# CNC.net
KiCad netlist of a schematic drawn in Altium Designer
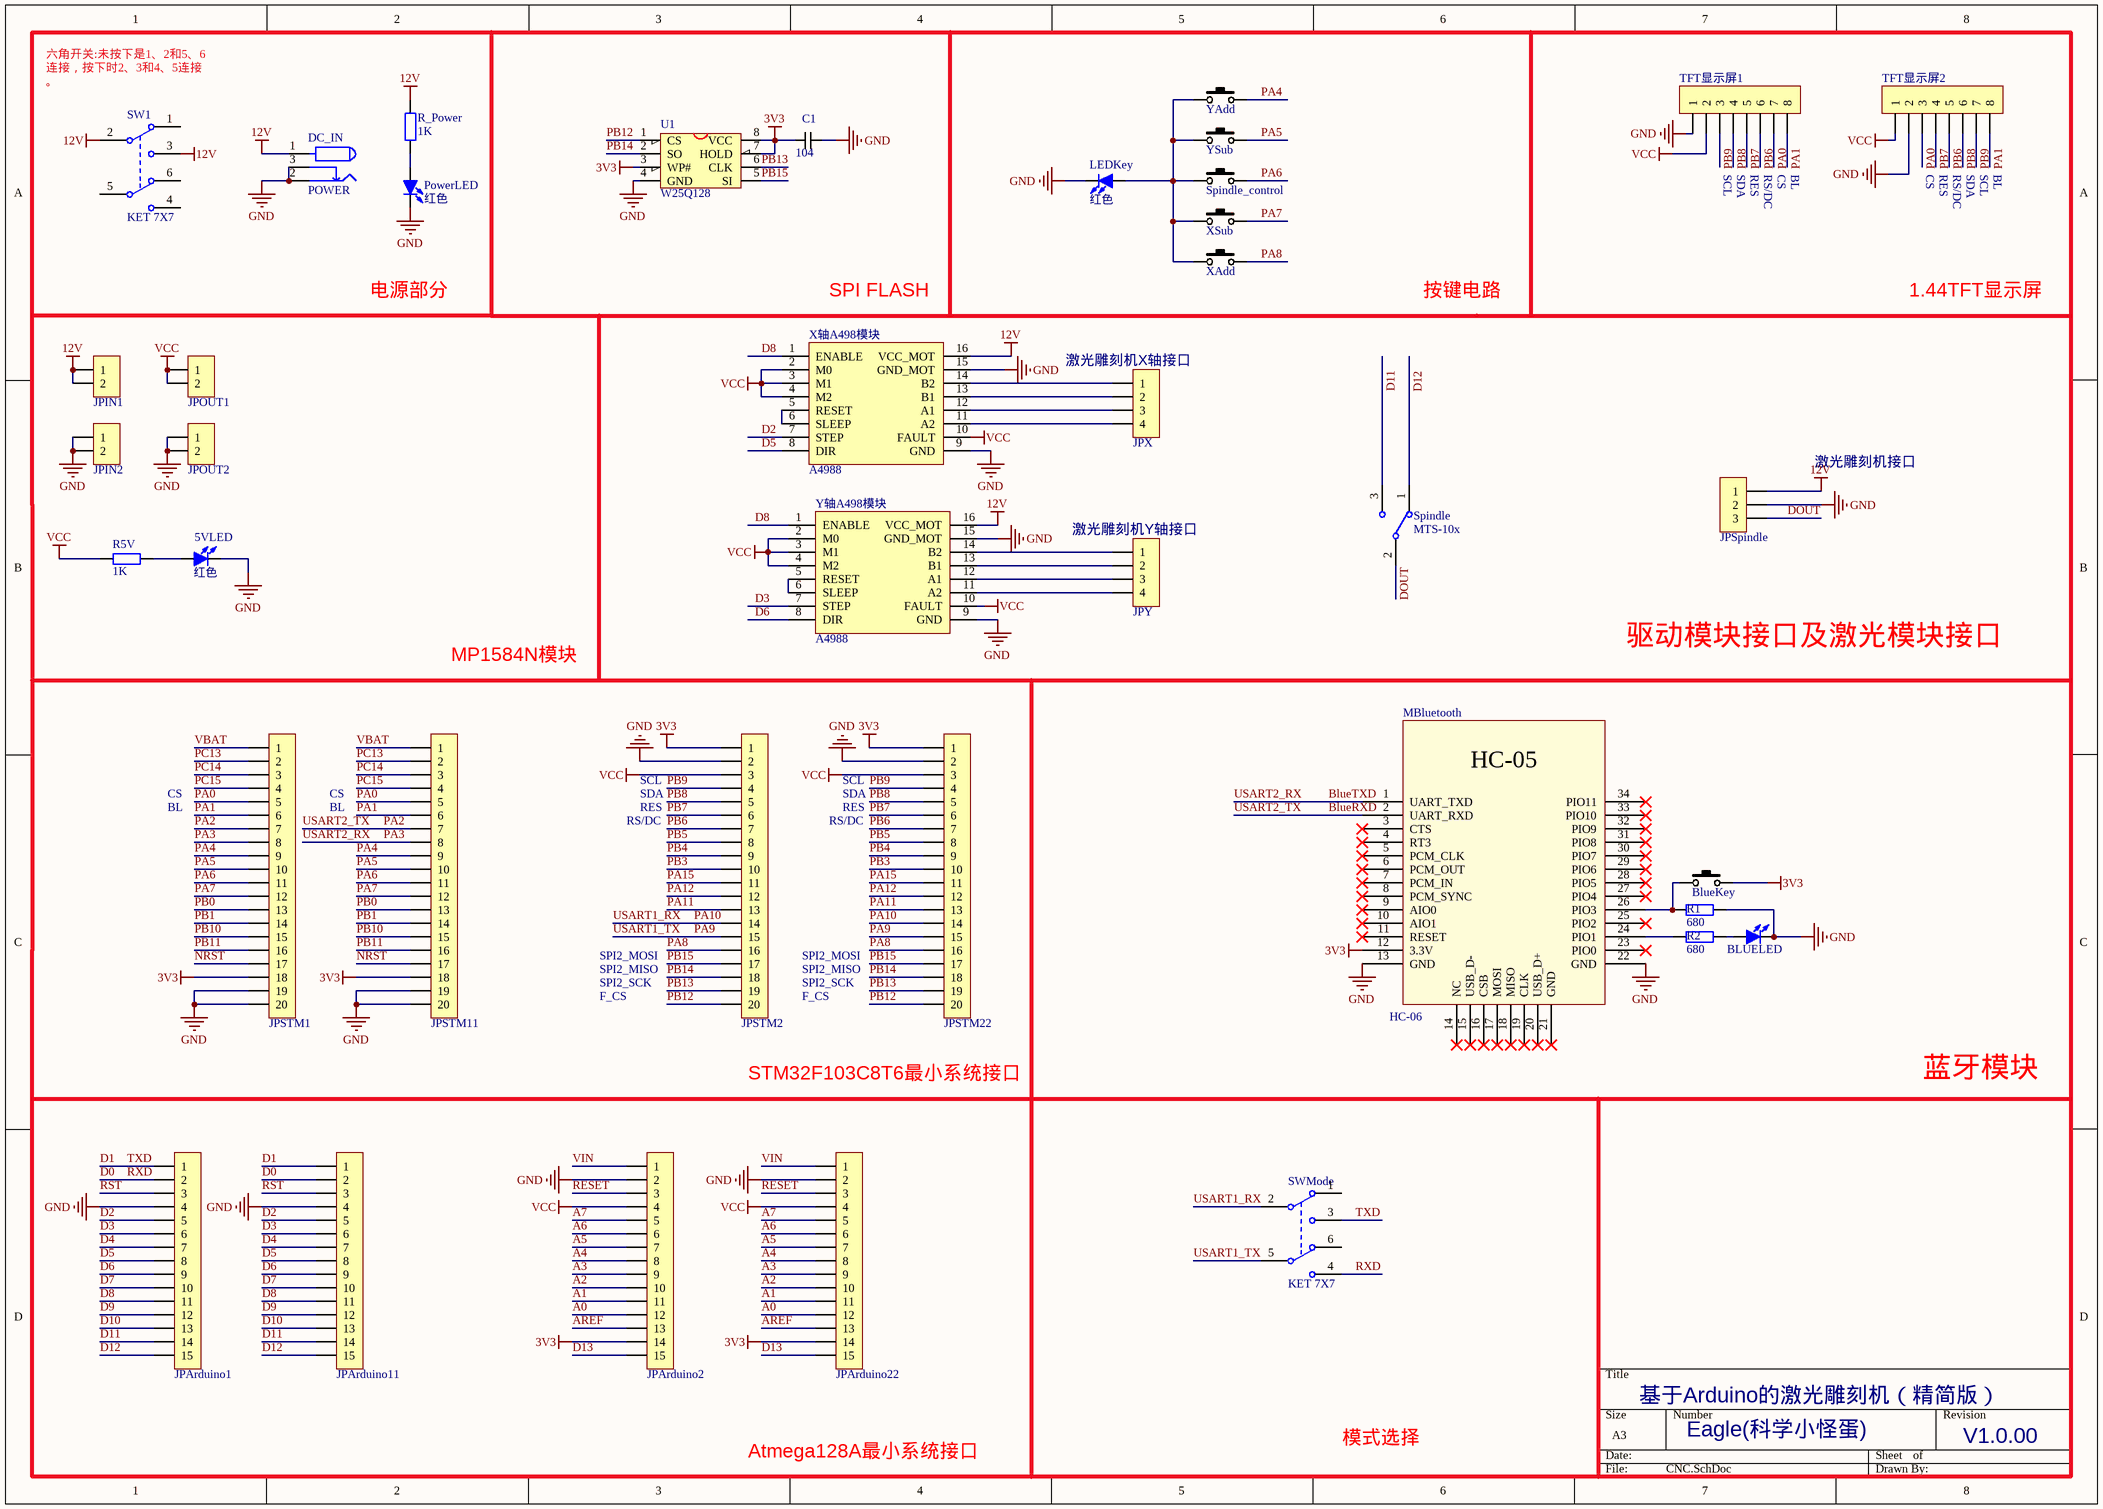
[diagram p0: CNC.SchDoc]

(export (version "E")
  (design (tool "Eeschema 10.0.6"))
  (components
    (comp (ref "5VLED")
      (value "红色")
      (footprint "LED 3MM-B")
      (description "插件LED")
      (fields (field (name "版权归属") "源创客"))
      (libsource (lib "9.1   - LED") (part "LED-3MM"))
    )
    (comp (ref "BlueKey")
      (value "Key")
      (footprint "SW-PB")
      (description "按键")
      (libsource (lib "Component") (part "Key"))
    )
    (comp (ref "BLUELED")
      (value "红色")
      (footprint "LED 0805R")
      (description "贴片LED")
      (fields (field (name "版权归属") "源创客"))
      (libsource (lib "9.1   - LED") (part "LED-SMD"))
    )
    (comp (ref "C1")
      (value "cap")
      (footprint "C0805")
      (description "电容")
      (fields (field (name "ALTIUM_UNNAMED_1") "104"))
      (libsource (lib "Component") (part "Cap"))
    )
    (comp (ref "DC_IN") (value "POWER") (footprint "DC10B") (libsource (lib "WARSHIP") (part "POW")))
    (comp (ref "JPArduino1")
      (value "HDR-1X15")
      (footprint "HDR2.54-LI-15P")
      (description "15P接插件")
      (fields (field (name "版权归属") "源创客"))
      (libsource (lib "4.5   - 接插件-脚距2.54") (part "Header 15"))
    )
    (comp (ref "JPArduino2")
      (value "HDR-1X15")
      (footprint "HDR2.54-LI-15P")
      (description "15P接插件")
      (fields (field (name "版权归属") "源创客"))
      (libsource (lib "4.5   - 接插件-脚距2.54") (part "Header 15"))
    )
    (comp (ref "JPArduino11")
      (value "HDR-1X15")
      (footprint "HDR2.54-LI-15P")
      (description "15P接插件")
      (fields (field (name "版权归属") "源创客"))
      (libsource (lib "4.5   - 接插件-脚距2.54") (part "Header 15"))
    )
    (comp (ref "JPArduino22")
      (value "HDR-1X15")
      (footprint "HDR2.54-LI-15P")
      (description "15P接插件")
      (fields (field (name "版权归属") "源创客"))
      (libsource (lib "4.5   - 接插件-脚距2.54") (part "Header 15"))
    )
    (comp (ref "JPIN1")
      (value "HDR-1X2")
      (footprint "HDR2.54-LI-2P")
      (description "2P接插件")
      (fields (field (name "版权归属") "源创客"))
      (libsource (lib "4.5   - 接插件-脚距2.54") (part "Header 2"))
    )
    (comp (ref "JPIN2")
      (value "HDR-1X2")
      (footprint "HDR2.54-LI-2P")
      (description "2P接插件")
      (fields (field (name "版权归属") "源创客"))
      (libsource (lib "4.5   - 接插件-脚距2.54") (part "Header 2"))
    )
    (comp (ref "JPOUT1")
      (value "HDR-1X2")
      (footprint "HDR2.54-LI-2P")
      (description "2P接插件")
      (fields (field (name "版权归属") "源创客"))
      (libsource (lib "4.5   - 接插件-脚距2.54") (part "Header 2"))
    )
    (comp (ref "JPOUT2")
      (value "HDR-1X2")
      (footprint "HDR2.54-LI-2P")
      (description "2P接插件")
      (fields (field (name "版权归属") "源创客"))
      (libsource (lib "4.5   - 接插件-脚距2.54") (part "Header 2"))
    )
    (comp (ref "JPSpindle")
      (value "HDR-1X3")
      (footprint "XH2.54-WI-3P")
      (description "3P接插件")
      (fields (field (name "版权归属") "源创客"))
      (libsource (lib "4.5   - 接插件-脚距2.54") (part "Header 3"))
    )
    (comp (ref "JPSTM1")
      (value "HDR-1X20")
      (footprint "HDR2.54-LI-20P")
      (description "20P接插件")
      (fields (field (name "版权归属") "源创客"))
      (libsource (lib "4.5   - 接插件-脚距2.54") (part "Header 20"))
    )
    (comp (ref "JPSTM2")
      (value "HDR-1X20")
      (footprint "HDR2.54-LI-20P")
      (description "20P接插件")
      (fields (field (name "版权归属") "源创客"))
      (libsource (lib "4.5   - 接插件-脚距2.54") (part "Header 20"))
    )
    (comp (ref "JPSTM11")
      (value "HDR-1X20")
      (footprint "HDR2.54-LI-20P")
      (description "20P接插件")
      (fields (field (name "版权归属") "源创客"))
      (libsource (lib "4.5   - 接插件-脚距2.54") (part "Header 20"))
    )
    (comp (ref "JPSTM22")
      (value "HDR-1X20")
      (footprint "HDR2.54-LI-20P")
      (description "20P接插件")
      (fields (field (name "版权归属") "源创客"))
      (libsource (lib "4.5   - 接插件-脚距2.54") (part "Header 20"))
    )
    (comp (ref "JPX")
      (value "HDR-1X4")
      (footprint "XH2.54-WI-4P")
      (description "4P接插件")
      (fields (field (name "版权归属") "源创客"))
      (libsource (lib "4.5   - 接插件-脚距2.54") (part "Header 4"))
    )
    (comp (ref "JPY")
      (value "HDR-1X4")
      (footprint "XH2.54-WI-4P")
      (description "4P接插件")
      (fields (field (name "版权归属") "源创客"))
      (libsource (lib "4.5   - 接插件-脚距2.54") (part "Header 4"))
    )
    (comp (ref "LEDKey")
      (value "红色")
      (footprint "LED 5MM-B")
      (description "5mm插件LED")
      (fields (field (name "版权归属") "源创客"))
      (libsource (lib "9.1   - LED") (part "LED-5MM"))
    )
    (comp (ref "MBluetooth")
      (value "HC-06")
      (footprint "HC-05")
      (description "串口蓝牙模块")
      (fields (field (name "版权归属") "源创客"))
      (libsource (lib "13.1 - 模块") (part "HC-05"))
    )
    (comp (ref "PowerLED")
      (value "红色")
      (footprint "LED 3MM-B")
      (description "插件LED")
      (fields (field (name "版权归属") "源创客"))
      (libsource (lib "9.1   - LED") (part "LED-3MM"))
    )
    (comp (ref "R1")
      (value "680")
      (footprint "R 0805_L")
      (description "贴片电阻")
      (fields (field (name "版权归属") "源创客"))
      (libsource (lib "3.1   - 电阻-电容-电感") (part "R"))
    )
    (comp (ref "R2")
      (value "680")
      (footprint "R 0805_L")
      (description "贴片电阻")
      (fields (field (name "版权归属") "源创客"))
      (libsource (lib "3.1   - 电阻-电容-电感") (part "R"))
    )
    (comp (ref "R5V")
      (value "1K")
      (footprint "RS 1/4W")
      (description "直插色环电阻")
      (fields (field (name "版权归属") "源创客"))
      (libsource (lib "3.1   - 电阻-电容-电感") (part "R-CRR"))
    )
    (comp (ref "R_Power")
      (value "1K")
      (footprint "RS 1/4W")
      (description "直插色环电阻")
      (fields (field (name "版权归属") "源创客"))
      (libsource (lib "3.1   - 电阻-电容-电感") (part "R-CRR"))
    )
    (comp (ref "Spindle")
      (value "MTS-10x")
      (footprint "MTS-10x")
      (description "MTS10x系列3脚扭子开关")
      (fields (field (name "版权归属") "源创客"))
      (libsource (lib "5.1   - 按键-开关") (part "MTS-10x"))
    )
    (comp (ref "Spindle_control")
      (value "Key")
      (footprint "SW-PB")
      (description "按键")
      (libsource (lib "Component") (part "Key"))
    )
    (comp (ref "SW1")
      (value "KET 7X7")
      (footprint "KFT DIP-7X7")
      (description "7*7自锁开关")
      (fields (field (name "版权归属") "源创客"))
      (libsource (lib "5.1   - 按键-开关") (part "KET 7X7"))
    )
    (comp (ref "SWMode")
      (value "KET 7X7")
      (footprint "KFT DIP-7X7")
      (description "7*7自锁开关")
      (fields (field (name "版权归属") "源创客"))
      (libsource (lib "5.1   - 按键-开关") (part "KET 7X7"))
    )
    (comp (ref "TFT显示屏1")
      (value "HDR-1X8")
      (footprint "HDR2.54-Y-LI-8P")
      (description "8P接插件")
      (fields (field (name "版权归属") "源创客"))
      (libsource (lib "4.5   - 接插件-脚距2.54") (part "Header 8"))
    )
    (comp (ref "TFT显示屏2")
      (value "HDR-1X8")
      (footprint "HDR2.54-Y-LI-8P")
      (description "8P接插件")
      (fields (field (name "版权归属") "源创客"))
      (libsource (lib "4.5   - 接插件-脚距2.54") (part "Header 8"))
    )
    (comp (ref "U1")
      (value "W25Q128")
      (footprint "SOIC-8")
      (description "W25X16;SST25VF016;MX25L1605")
      (libsource (lib "WARSHIP") (part "W25X16"))
    )
    (comp (ref "XAdd")
      (value "Key")
      (footprint "SW-PB")
      (description "按键")
      (libsource (lib "Component") (part "Key"))
    )
    (comp (ref "XSub")
      (value "Key")
      (footprint "SW-PB")
      (description "按键")
      (libsource (lib "Component") (part "Key"))
    )
    (comp (ref "X轴A498模块")
      (value "A4988")
      (footprint "DRV8825")
      (description "步进电机驱动模块")
      (fields (field (name "版权归属") "源创客"))
      (libsource (lib "13.1 - 模块") (part "DRV8825"))
    )
    (comp (ref "YAdd")
      (value "Key")
      (footprint "SW-PB")
      (description "按键")
      (libsource (lib "Component") (part "Key"))
    )
    (comp (ref "YSub")
      (value "Key")
      (footprint "SW-PB")
      (description "按键")
      (libsource (lib "Component") (part "Key"))
    )
    (comp (ref "Y轴A498模块")
      (value "A4988")
      (footprint "DRV8825")
      (description "步进电机驱动模块")
      (fields (field (name "版权归属") "源创客"))
      (libsource (lib "13.1 - 模块") (part "DRV8825"))
    )
  )
  (nets
    (net (code "1") (name "/A0") (class "Default")
      (node (ref "JPArduino2") (pin "12") (pinfunction "12_12") (pintype "passive"))
      (node (ref "JPArduino22") (pin "12") (pinfunction "12_12") (pintype "passive"))
    )
    (net (code "2") (name "/A1") (class "Default")
      (node (ref "JPArduino2") (pin "11") (pinfunction "11_11") (pintype "passive"))
      (node (ref "JPArduino22") (pin "11") (pinfunction "11_11") (pintype "passive"))
    )
    (net (code "3") (name "/A2") (class "Default")
      (node (ref "JPArduino2") (pin "10") (pinfunction "10_10") (pintype "passive"))
      (node (ref "JPArduino22") (pin "10") (pinfunction "10_10") (pintype "passive"))
    )
    (net (code "4") (name "/A3") (class "Default")
      (node (ref "JPArduino2") (pin "9") (pinfunction "9_9") (pintype "passive"))
      (node (ref "JPArduino22") (pin "9") (pinfunction "9_9") (pintype "passive"))
    )
    (net (code "5") (name "/A4") (class "Default")
      (node (ref "JPArduino2") (pin "8") (pinfunction "8_8") (pintype "passive"))
      (node (ref "JPArduino22") (pin "8") (pinfunction "8_8") (pintype "passive"))
    )
    (net (code "6") (name "/A5") (class "Default")
      (node (ref "JPArduino2") (pin "7") (pinfunction "7_7") (pintype "passive"))
      (node (ref "JPArduino22") (pin "7") (pinfunction "7_7") (pintype "passive"))
    )
    (net (code "7") (name "/A6") (class "Default")
      (node (ref "JPArduino2") (pin "6") (pinfunction "6_6") (pintype "passive"))
      (node (ref "JPArduino22") (pin "6") (pinfunction "6_6") (pintype "passive"))
    )
    (net (code "8") (name "/A7") (class "Default")
      (node (ref "JPArduino2") (pin "5") (pinfunction "5_5") (pintype "passive"))
      (node (ref "JPArduino22") (pin "5") (pinfunction "5_5") (pintype "passive"))
    )
    (net (code "9") (name "/AREF") (class "Default")
      (node (ref "JPArduino2") (pin "13") (pinfunction "13_13") (pintype "passive"))
      (node (ref "JPArduino22") (pin "13") (pinfunction "13_13") (pintype "passive"))
    )
    (net (code "10") (name "/BlueRXD") (class "Default")
      (node (ref "JPSTM1") (pin "7") (pinfunction "7_7") (pintype "passive"))
      (node (ref "JPSTM11") (pin "7") (pinfunction "7_7") (pintype "passive"))
      (node (ref "MBluetooth") (pin "2") (pinfunction "UART_RXD_2") (pintype "passive"))
    )
    (net (code "11") (name "/BlueTXD") (class "Default")
      (node (ref "JPSTM1") (pin "8") (pinfunction "8_8") (pintype "passive"))
      (node (ref "JPSTM11") (pin "8") (pinfunction "8_8") (pintype "passive"))
      (node (ref "MBluetooth") (pin "1") (pinfunction "UART_TXD_1") (pintype "passive"))
    )
    (net (code "12") (name "/D0") (class "Default")
      (node (ref "JPArduino1") (pin "2") (pinfunction "2_2") (pintype "passive"))
      (node (ref "JPArduino11") (pin "2") (pinfunction "2_2") (pintype "passive"))
      (node (ref "SWMode") (pin "4") (pinfunction "NO2_4") (pintype "passive"))
    )
    (net (code "13") (name "/D1") (class "Default")
      (node (ref "JPArduino1") (pin "1") (pinfunction "1_1") (pintype "passive"))
      (node (ref "JPArduino11") (pin "1") (pinfunction "1_1") (pintype "passive"))
      (node (ref "SWMode") (pin "3") (pinfunction "NO1_3") (pintype "passive"))
    )
    (net (code "14") (name "/D2") (class "Default")
      (node (ref "JPArduino1") (pin "5") (pinfunction "5_5") (pintype "passive"))
      (node (ref "JPArduino11") (pin "5") (pinfunction "5_5") (pintype "passive"))
      (node (ref "X轴A498模块") (pin "7") (pinfunction "STEP_7") (pintype "passive"))
    )
    (net (code "15") (name "/D3") (class "Default")
      (node (ref "JPArduino1") (pin "6") (pinfunction "6_6") (pintype "passive"))
      (node (ref "JPArduino11") (pin "6") (pinfunction "6_6") (pintype "passive"))
      (node (ref "Y轴A498模块") (pin "7") (pinfunction "STEP_7") (pintype "passive"))
    )
    (net (code "16") (name "/D4") (class "Default")
      (node (ref "JPArduino1") (pin "7") (pinfunction "7_7") (pintype "passive"))
      (node (ref "JPArduino11") (pin "7") (pinfunction "7_7") (pintype "passive"))
    )
    (net (code "17") (name "/D5") (class "Default")
      (node (ref "JPArduino1") (pin "8") (pinfunction "8_8") (pintype "passive"))
      (node (ref "JPArduino11") (pin "8") (pinfunction "8_8") (pintype "passive"))
      (node (ref "X轴A498模块") (pin "8") (pinfunction "DIR_8") (pintype "passive"))
    )
    (net (code "18") (name "/D6") (class "Default")
      (node (ref "JPArduino1") (pin "9") (pinfunction "9_9") (pintype "passive"))
      (node (ref "JPArduino11") (pin "9") (pinfunction "9_9") (pintype "passive"))
      (node (ref "Y轴A498模块") (pin "8") (pinfunction "DIR_8") (pintype "passive"))
    )
    (net (code "19") (name "/D7") (class "Default")
      (node (ref "JPArduino1") (pin "10") (pinfunction "10_10") (pintype "passive"))
      (node (ref "JPArduino11") (pin "10") (pinfunction "10_10") (pintype "passive"))
    )
    (net (code "20") (name "/D8") (class "Default")
      (node (ref "JPArduino1") (pin "11") (pinfunction "11_11") (pintype "passive"))
      (node (ref "JPArduino11") (pin "11") (pinfunction "11_11") (pintype "passive"))
      (node (ref "X轴A498模块") (pin "1") (pinfunction "ENABLE_1") (pintype "passive"))
      (node (ref "Y轴A498模块") (pin "1") (pinfunction "ENABLE_1") (pintype "passive"))
    )
    (net (code "21") (name "/D9") (class "Default")
      (node (ref "JPArduino1") (pin "12") (pinfunction "12_12") (pintype "passive"))
      (node (ref "JPArduino11") (pin "12") (pinfunction "12_12") (pintype "passive"))
    )
    (net (code "22") (name "/D10") (class "Default")
      (node (ref "JPArduino1") (pin "13") (pinfunction "13_13") (pintype "passive"))
      (node (ref "JPArduino11") (pin "13") (pinfunction "13_13") (pintype "passive"))
    )
    (net (code "23") (name "/D11") (class "Default")
      (node (ref "JPArduino1") (pin "14") (pinfunction "14_14") (pintype "passive"))
      (node (ref "JPArduino11") (pin "14") (pinfunction "14_14") (pintype "passive"))
      (node (ref "Spindle") (pin "3") (pinfunction "3_3") (pintype "passive"))
    )
    (net (code "24") (name "/D12") (class "Default")
      (node (ref "JPArduino1") (pin "15") (pinfunction "15_15") (pintype "passive"))
      (node (ref "JPArduino11") (pin "15") (pinfunction "15_15") (pintype "passive"))
      (node (ref "Spindle") (pin "1") (pinfunction "1_1") (pintype "passive"))
    )
    (net (code "25") (name "/D13") (class "Default")
      (node (ref "JPArduino2") (pin "15") (pinfunction "15_15") (pintype "passive"))
      (node (ref "JPArduino22") (pin "15") (pinfunction "15_15") (pintype "passive"))
    )
    (net (code "26") (name "/DOUT") (class "Default")
      (node (ref "JPSpindle") (pin "3") (pinfunction "3_3") (pintype "passive"))
      (node (ref "Spindle") (pin "2") (pinfunction "2_2") (pintype "passive"))
    )
    (net (code "27") (name "/NRST") (class "Default")
      (node (ref "JPSTM1") (pin "17") (pinfunction "17_17") (pintype "passive"))
      (node (ref "JPSTM11") (pin "17") (pinfunction "17_17") (pintype "passive"))
    )
    (net (code "28") (name "/PA0") (class "Default")
      (node (ref "JPSTM1") (pin "5") (pinfunction "5_5") (pintype "passive"))
      (node (ref "JPSTM11") (pin "5") (pinfunction "5_5") (pintype "passive"))
      (node (ref "TFT显示屏1") (pin "7") (pinfunction "7_7") (pintype "passive"))
      (node (ref "TFT显示屏2") (pin "3") (pinfunction "3_3") (pintype "passive"))
    )
    (net (code "29") (name "/PA1") (class "Default")
      (node (ref "JPSTM1") (pin "6") (pinfunction "6_6") (pintype "passive"))
      (node (ref "JPSTM11") (pin "6") (pinfunction "6_6") (pintype "passive"))
      (node (ref "TFT显示屏1") (pin "8") (pinfunction "8_8") (pintype "passive"))
      (node (ref "TFT显示屏2") (pin "8") (pinfunction "8_8") (pintype "passive"))
    )
    (net (code "30") (name "/PA4") (class "Default")
      (node (ref "JPSTM1") (pin "9") (pinfunction "9_9") (pintype "passive"))
      (node (ref "JPSTM11") (pin "9") (pinfunction "9_9") (pintype "passive"))
      (node (ref "YAdd") (pin "3") (pintype "passive"))
    )
    (net (code "31") (name "/PA5") (class "Default")
      (node (ref "JPSTM1") (pin "10") (pinfunction "10_10") (pintype "passive"))
      (node (ref "JPSTM11") (pin "10") (pinfunction "10_10") (pintype "passive"))
      (node (ref "YSub") (pin "3") (pintype "passive"))
    )
    (net (code "32") (name "/PA6") (class "Default")
      (node (ref "JPSTM1") (pin "11") (pinfunction "11_11") (pintype "passive"))
      (node (ref "JPSTM11") (pin "11") (pinfunction "11_11") (pintype "passive"))
      (node (ref "Spindle_control") (pin "3") (pintype "passive"))
    )
    (net (code "33") (name "/PA7") (class "Default")
      (node (ref "JPSTM1") (pin "12") (pinfunction "12_12") (pintype "passive"))
      (node (ref "JPSTM11") (pin "12") (pinfunction "12_12") (pintype "passive"))
      (node (ref "XSub") (pin "3") (pintype "passive"))
    )
    (net (code "34") (name "/PA8") (class "Default")
      (node (ref "JPSTM2") (pin "16") (pinfunction "16_16") (pintype "passive"))
      (node (ref "JPSTM22") (pin "16") (pinfunction "16_16") (pintype "passive"))
      (node (ref "XAdd") (pin "3") (pintype "passive"))
    )
    (net (code "35") (name "/PA9") (class "Default")
      (node (ref "JPSTM2") (pin "15") (pinfunction "15_15") (pintype "passive"))
      (node (ref "JPSTM22") (pin "15") (pinfunction "15_15") (pintype "passive"))
      (node (ref "SWMode") (pin "5") (pinfunction "COM2_5") (pintype "passive"))
    )
    (net (code "36") (name "/PA10") (class "Default")
      (node (ref "JPSTM2") (pin "14") (pinfunction "14_14") (pintype "passive"))
      (node (ref "JPSTM22") (pin "14") (pinfunction "14_14") (pintype "passive"))
      (node (ref "SWMode") (pin "2") (pinfunction "COM2_2") (pintype "passive"))
    )
    (net (code "37") (name "/PA11") (class "Default")
      (node (ref "JPSTM2") (pin "13") (pinfunction "13_13") (pintype "passive"))
      (node (ref "JPSTM22") (pin "13") (pinfunction "13_13") (pintype "passive"))
    )
    (net (code "38") (name "/PA12") (class "Default")
      (node (ref "JPSTM2") (pin "12") (pinfunction "12_12") (pintype "passive"))
      (node (ref "JPSTM22") (pin "12") (pinfunction "12_12") (pintype "passive"))
    )
    (net (code "39") (name "/PA15") (class "Default")
      (node (ref "JPSTM2") (pin "11") (pinfunction "11_11") (pintype "passive"))
      (node (ref "JPSTM22") (pin "11") (pinfunction "11_11") (pintype "passive"))
    )
    (net (code "40") (name "/PB0") (class "Default")
      (node (ref "JPSTM1") (pin "13") (pinfunction "13_13") (pintype "passive"))
      (node (ref "JPSTM11") (pin "13") (pinfunction "13_13") (pintype "passive"))
    )
    (net (code "41") (name "/PB1") (class "Default")
      (node (ref "JPSTM1") (pin "14") (pinfunction "14_14") (pintype "passive"))
      (node (ref "JPSTM11") (pin "14") (pinfunction "14_14") (pintype "passive"))
    )
    (net (code "42") (name "/PB3") (class "Default")
      (node (ref "JPSTM2") (pin "10") (pinfunction "10_10") (pintype "passive"))
      (node (ref "JPSTM22") (pin "10") (pinfunction "10_10") (pintype "passive"))
    )
    (net (code "43") (name "/PB4") (class "Default")
      (node (ref "JPSTM2") (pin "9") (pinfunction "9_9") (pintype "passive"))
      (node (ref "JPSTM22") (pin "9") (pinfunction "9_9") (pintype "passive"))
    )
    (net (code "44") (name "/PB5") (class "Default")
      (node (ref "JPSTM2") (pin "8") (pinfunction "8_8") (pintype "passive"))
      (node (ref "JPSTM22") (pin "8") (pinfunction "8_8") (pintype "passive"))
    )
    (net (code "45") (name "/PB6") (class "Default")
      (node (ref "JPSTM2") (pin "7") (pinfunction "7_7") (pintype "passive"))
      (node (ref "JPSTM22") (pin "7") (pinfunction "7_7") (pintype "passive"))
      (node (ref "TFT显示屏1") (pin "6") (pinfunction "6_6") (pintype "passive"))
      (node (ref "TFT显示屏2") (pin "5") (pinfunction "5_5") (pintype "passive"))
    )
    (net (code "46") (name "/PB7") (class "Default")
      (node (ref "JPSTM2") (pin "6") (pinfunction "6_6") (pintype "passive"))
      (node (ref "JPSTM22") (pin "6") (pinfunction "6_6") (pintype "passive"))
      (node (ref "TFT显示屏1") (pin "5") (pinfunction "5_5") (pintype "passive"))
      (node (ref "TFT显示屏2") (pin "4") (pinfunction "4_4") (pintype "passive"))
    )
    (net (code "47") (name "/PB8") (class "Default")
      (node (ref "JPSTM2") (pin "5") (pinfunction "5_5") (pintype "passive"))
      (node (ref "JPSTM22") (pin "5") (pinfunction "5_5") (pintype "passive"))
      (node (ref "TFT显示屏1") (pin "4") (pinfunction "4_4") (pintype "passive"))
      (node (ref "TFT显示屏2") (pin "6") (pinfunction "6_6") (pintype "passive"))
    )
    (net (code "48") (name "/PB9") (class "Default")
      (node (ref "JPSTM2") (pin "4") (pinfunction "4_4") (pintype "passive"))
      (node (ref "JPSTM22") (pin "4") (pinfunction "4_4") (pintype "passive"))
      (node (ref "TFT显示屏1") (pin "3") (pinfunction "3_3") (pintype "passive"))
      (node (ref "TFT显示屏2") (pin "7") (pinfunction "7_7") (pintype "passive"))
    )
    (net (code "49") (name "/PB10") (class "Default")
      (node (ref "JPSTM1") (pin "15") (pinfunction "15_15") (pintype "passive"))
      (node (ref "JPSTM11") (pin "15") (pinfunction "15_15") (pintype "passive"))
    )
    (net (code "50") (name "/PB11") (class "Default")
      (node (ref "JPSTM1") (pin "16") (pinfunction "16_16") (pintype "passive"))
      (node (ref "JPSTM11") (pin "16") (pinfunction "16_16") (pintype "passive"))
    )
    (net (code "51") (name "/PB12") (class "Default")
      (node (ref "JPSTM2") (pin "20") (pinfunction "20_20") (pintype "passive"))
      (node (ref "JPSTM22") (pin "20") (pinfunction "20_20") (pintype "passive"))
      (node (ref "U1") (pin "1") (pinfunction "CS_1") (pintype "passive"))
    )
    (net (code "52") (name "/PB13") (class "Default")
      (node (ref "JPSTM2") (pin "19") (pinfunction "19_19") (pintype "passive"))
      (node (ref "JPSTM22") (pin "19") (pinfunction "19_19") (pintype "passive"))
      (node (ref "U1") (pin "6") (pinfunction "CLK_6") (pintype "passive"))
    )
    (net (code "53") (name "/PB14") (class "Default")
      (node (ref "JPSTM2") (pin "18") (pinfunction "18_18") (pintype "passive"))
      (node (ref "JPSTM22") (pin "18") (pinfunction "18_18") (pintype "passive"))
      (node (ref "U1") (pin "2") (pinfunction "SO_2") (pintype "passive"))
    )
    (net (code "54") (name "/PB15") (class "Default")
      (node (ref "JPSTM2") (pin "17") (pinfunction "17_17") (pintype "passive"))
      (node (ref "JPSTM22") (pin "17") (pinfunction "17_17") (pintype "passive"))
      (node (ref "U1") (pin "5") (pinfunction "SI_5") (pintype "passive"))
    )
    (net (code "55") (name "/PC13") (class "Default")
      (node (ref "JPSTM1") (pin "2") (pinfunction "2_2") (pintype "passive"))
      (node (ref "JPSTM11") (pin "2") (pinfunction "2_2") (pintype "passive"))
    )
    (net (code "56") (name "/PC14") (class "Default")
      (node (ref "JPSTM1") (pin "3") (pinfunction "3_3") (pintype "passive"))
      (node (ref "JPSTM11") (pin "3") (pinfunction "3_3") (pintype "passive"))
    )
    (net (code "57") (name "/PC15") (class "Default")
      (node (ref "JPSTM1") (pin "4") (pinfunction "4_4") (pintype "passive"))
      (node (ref "JPSTM11") (pin "4") (pinfunction "4_4") (pintype "passive"))
    )
    (net (code "58") (name "/RESET") (class "Default")
      (node (ref "JPArduino2") (pin "3") (pinfunction "3_3") (pintype "passive"))
      (node (ref "JPArduino22") (pin "3") (pinfunction "3_3") (pintype "passive"))
    )
    (net (code "59") (name "/RST") (class "Default")
      (node (ref "JPArduino1") (pin "3") (pinfunction "3_3") (pintype "passive"))
      (node (ref "JPArduino11") (pin "3") (pinfunction "3_3") (pintype "passive"))
    )
    (net (code "60") (name "/VBAT") (class "Default")
      (node (ref "JPSTM1") (pin "1") (pinfunction "1_1") (pintype "passive"))
      (node (ref "JPSTM11") (pin "1") (pinfunction "1_1") (pintype "passive"))
    )
    (net (code "61") (name "/VIN") (class "Default")
      (node (ref "JPArduino2") (pin "1") (pinfunction "1_1") (pintype "passive"))
      (node (ref "JPArduino22") (pin "1") (pinfunction "1_1") (pintype "passive"))
    )
    (net (code "62") (name "3V3") (class "Default")
      (node (ref "BlueKey") (pin "3") (pintype "passive"))
      (node (ref "C1") (pin "1") (pintype "passive"))
      (node (ref "JPArduino2") (pin "14") (pinfunction "14_14") (pintype "passive"))
      (node (ref "JPArduino22") (pin "14") (pinfunction "14_14") (pintype "passive"))
      (node (ref "JPSTM1") (pin "18") (pinfunction "18_18") (pintype "passive"))
      (node (ref "JPSTM11") (pin "18") (pinfunction "18_18") (pintype "passive"))
      (node (ref "JPSTM2") (pin "1") (pinfunction "1_1") (pintype "passive"))
      (node (ref "JPSTM22") (pin "1") (pinfunction "1_1") (pintype "passive"))
      (node (ref "MBluetooth") (pin "12") (pinfunction "3.3V_12") (pintype "passive"))
      (node (ref "U1") (pin "3") (pinfunction "WP#_3") (pintype "passive"))
      (node (ref "U1") (pin "7") (pinfunction "HOLD_7") (pintype "passive"))
      (node (ref "U1") (pin "8") (pinfunction "VCC_8") (pintype "passive"))
    )
    (net (code "63") (name "12V") (class "Default")
      (node (ref "DC_IN") (pin "1") (pintype "passive"))
      (node (ref "JPIN1") (pin "1") (pinfunction "1_1") (pintype "passive"))
      (node (ref "JPIN1") (pin "2") (pinfunction "2_2") (pintype "passive"))
      (node (ref "JPSpindle") (pin "1") (pinfunction "1_1") (pintype "passive"))
      (node (ref "R_Power") (pin "2") (pinfunction "2_2") (pintype "passive"))
      (node (ref "SW1") (pin "2") (pinfunction "COM2_2") (pintype "passive"))
      (node (ref "SW1") (pin "3") (pinfunction "NO1_3") (pintype "passive"))
      (node (ref "X轴A498模块") (pin "16") (pinfunction "VCC_MOT_16") (pintype "passive"))
      (node (ref "Y轴A498模块") (pin "16") (pinfunction "VCC_MOT_16") (pintype "passive"))
    )
    (net (code "64") (name "GND") (class "Default")
      (node (ref "5VLED") (pin "2") (pinfunction "K_2") (pintype "passive"))
      (node (ref "BLUELED") (pin "2") (pinfunction "K_2") (pintype "passive"))
      (node (ref "C1") (pin "2") (pintype "passive"))
      (node (ref "DC_IN") (pin "2") (pintype "passive"))
      (node (ref "DC_IN") (pin "3") (pintype "passive"))
      (node (ref "JPArduino1") (pin "4") (pinfunction "4_4") (pintype "passive"))
      (node (ref "JPArduino11") (pin "4") (pinfunction "4_4") (pintype "passive"))
      (node (ref "JPArduino2") (pin "2") (pinfunction "2_2") (pintype "passive"))
      (node (ref "JPArduino22") (pin "2") (pinfunction "2_2") (pintype "passive"))
      (node (ref "JPIN2") (pin "1") (pinfunction "1_1") (pintype "passive"))
      (node (ref "JPIN2") (pin "2") (pinfunction "2_2") (pintype "passive"))
      (node (ref "JPOUT2") (pin "1") (pinfunction "1_1") (pintype "passive"))
      (node (ref "JPOUT2") (pin "2") (pinfunction "2_2") (pintype "passive"))
      (node (ref "JPSTM1") (pin "19") (pinfunction "19_19") (pintype "passive"))
      (node (ref "JPSTM1") (pin "20") (pinfunction "20_20") (pintype "passive"))
      (node (ref "JPSTM11") (pin "19") (pinfunction "19_19") (pintype "passive"))
      (node (ref "JPSTM11") (pin "20") (pinfunction "20_20") (pintype "passive"))
      (node (ref "JPSTM2") (pin "2") (pinfunction "2_2") (pintype "passive"))
      (node (ref "JPSTM22") (pin "2") (pinfunction "2_2") (pintype "passive"))
      (node (ref "JPSpindle") (pin "2") (pinfunction "2_2") (pintype "passive"))
      (node (ref "LEDKey") (pin "2") (pinfunction "K_2") (pintype "passive"))
      (node (ref "MBluetooth") (pin "13") (pinfunction "GND_13") (pintype "passive"))
      (node (ref "MBluetooth") (pin "22") (pinfunction "GND_22") (pintype "passive"))
      (node (ref "PowerLED") (pin "2") (pinfunction "K_2") (pintype "passive"))
      (node (ref "R1") (pin "1") (pinfunction "1_1") (pintype "passive"))
      (node (ref "TFT显示屏1") (pin "1") (pinfunction "1_1") (pintype "passive"))
      (node (ref "TFT显示屏2") (pin "2") (pinfunction "2_2") (pintype "passive"))
      (node (ref "U1") (pin "4") (pinfunction "GND_4") (pintype "passive"))
      (node (ref "X轴A498模块") (pin "15") (pinfunction "GND_MOT_15") (pintype "passive"))
      (node (ref "X轴A498模块") (pin "9") (pinfunction "GND_9") (pintype "passive"))
      (node (ref "Y轴A498模块") (pin "15") (pinfunction "GND_MOT_15") (pintype "passive"))
      (node (ref "Y轴A498模块") (pin "9") (pinfunction "GND_9") (pintype "passive"))
    )
    (net (code "65") (name "Net-(5VLED-A)") (class "Default")
      (node (ref "5VLED") (pin "1") (pinfunction "A_1") (pintype "passive"))
      (node (ref "R5V") (pin "2") (pinfunction "2_2") (pintype "passive"))
    )
    (net (code "66") (name "Net-(BLUELED-A)") (class "Default")
      (node (ref "BLUELED") (pin "1") (pinfunction "A_1") (pintype "passive"))
      (node (ref "R2") (pin "1") (pinfunction "1_1") (pintype "passive"))
    )
    (net (code "67") (name "Net-(LEDKey-A)") (class "Default")
      (node (ref "LEDKey") (pin "1") (pinfunction "A_1") (pintype "passive"))
      (node (ref "Spindle_control") (pin "1") (pintype "passive"))
      (node (ref "XAdd") (pin "1") (pintype "passive"))
      (node (ref "XSub") (pin "1") (pintype "passive"))
      (node (ref "YAdd") (pin "1") (pintype "passive"))
      (node (ref "YSub") (pin "1") (pintype "passive"))
    )
    (net (code "68") (name "Net-(MBluetooth-PIO1)") (class "Default")
      (node (ref "MBluetooth") (pin "24") (pinfunction "PIO1_24") (pintype "passive"))
      (node (ref "R2") (pin "2") (pinfunction "2_2") (pintype "passive"))
    )
    (net (code "69") (name "Net-(MBluetooth-PIO3)") (class "Default")
      (node (ref "BlueKey") (pin "1") (pintype "passive"))
      (node (ref "MBluetooth") (pin "26") (pinfunction "PIO3_26") (pintype "passive"))
      (node (ref "R1") (pin "2") (pinfunction "2_2") (pintype "passive"))
    )
    (net (code "70") (name "Net-(PowerLED-A)") (class "Default")
      (node (ref "PowerLED") (pin "1") (pinfunction "A_1") (pintype "passive"))
      (node (ref "R_Power") (pin "1") (pinfunction "1_1") (pintype "passive"))
    )
    (net (code "71") (name "Net-(X轴A498模块-A1)") (class "Default")
      (node (ref "JPX") (pin "3") (pinfunction "3_3") (pintype "passive"))
      (node (ref "X轴A498模块") (pin "12") (pinfunction "A1_12") (pintype "passive"))
    )
    (net (code "72") (name "Net-(X轴A498模块-A2)") (class "Default")
      (node (ref "JPX") (pin "4") (pinfunction "4_4") (pintype "passive"))
      (node (ref "X轴A498模块") (pin "11") (pinfunction "A2_11") (pintype "passive"))
    )
    (net (code "73") (name "Net-(X轴A498模块-B1)") (class "Default")
      (node (ref "JPX") (pin "2") (pinfunction "2_2") (pintype "passive"))
      (node (ref "X轴A498模块") (pin "13") (pinfunction "B1_13") (pintype "passive"))
    )
    (net (code "74") (name "Net-(X轴A498模块-B2)") (class "Default")
      (node (ref "JPX") (pin "1") (pinfunction "1_1") (pintype "passive"))
      (node (ref "X轴A498模块") (pin "14") (pinfunction "B2_14") (pintype "passive"))
    )
    (net (code "75") (name "Net-(X轴A498模块-RESET)") (class "Default")
      (node (ref "X轴A498模块") (pin "5") (pinfunction "RESET_5") (pintype "passive"))
      (node (ref "X轴A498模块") (pin "6") (pinfunction "SLEEP_6") (pintype "passive"))
    )
    (net (code "76") (name "Net-(Y轴A498模块-A1)") (class "Default")
      (node (ref "JPY") (pin "3") (pinfunction "3_3") (pintype "passive"))
      (node (ref "Y轴A498模块") (pin "12") (pinfunction "A1_12") (pintype "passive"))
    )
    (net (code "77") (name "Net-(Y轴A498模块-A2)") (class "Default")
      (node (ref "JPY") (pin "4") (pinfunction "4_4") (pintype "passive"))
      (node (ref "Y轴A498模块") (pin "11") (pinfunction "A2_11") (pintype "passive"))
    )
    (net (code "78") (name "Net-(Y轴A498模块-B1)") (class "Default")
      (node (ref "JPY") (pin "2") (pinfunction "2_2") (pintype "passive"))
      (node (ref "Y轴A498模块") (pin "13") (pinfunction "B1_13") (pintype "passive"))
    )
    (net (code "79") (name "Net-(Y轴A498模块-B2)") (class "Default")
      (node (ref "JPY") (pin "1") (pinfunction "1_1") (pintype "passive"))
      (node (ref "Y轴A498模块") (pin "14") (pinfunction "B2_14") (pintype "passive"))
    )
    (net (code "80") (name "Net-(Y轴A498模块-RESET)") (class "Default")
      (node (ref "Y轴A498模块") (pin "5") (pinfunction "RESET_5") (pintype "passive"))
      (node (ref "Y轴A498模块") (pin "6") (pinfunction "SLEEP_6") (pintype "passive"))
    )
    (net (code "81") (name "VCC") (class "Default")
      (node (ref "JPArduino2") (pin "4") (pinfunction "4_4") (pintype "passive"))
      (node (ref "JPArduino22") (pin "4") (pinfunction "4_4") (pintype "passive"))
      (node (ref "JPOUT1") (pin "1") (pinfunction "1_1") (pintype "passive"))
      (node (ref "JPOUT1") (pin "2") (pinfunction "2_2") (pintype "passive"))
      (node (ref "JPSTM2") (pin "3") (pinfunction "3_3") (pintype "passive"))
      (node (ref "JPSTM22") (pin "3") (pinfunction "3_3") (pintype "passive"))
      (node (ref "R5V") (pin "1") (pinfunction "1_1") (pintype "passive"))
      (node (ref "TFT显示屏1") (pin "2") (pinfunction "2_2") (pintype "passive"))
      (node (ref "TFT显示屏2") (pin "1") (pinfunction "1_1") (pintype "passive"))
      (node (ref "X轴A498模块") (pin "10") (pinfunction "FAULT_10") (pintype "passive"))
      (node (ref "X轴A498模块") (pin "2") (pinfunction "M0_2") (pintype "passive"))
      (node (ref "X轴A498模块") (pin "3") (pinfunction "M1_3") (pintype "passive"))
      (node (ref "X轴A498模块") (pin "4") (pinfunction "M2_4") (pintype "passive"))
      (node (ref "Y轴A498模块") (pin "10") (pinfunction "FAULT_10") (pintype "passive"))
      (node (ref "Y轴A498模块") (pin "2") (pinfunction "M0_2") (pintype "passive"))
      (node (ref "Y轴A498模块") (pin "3") (pinfunction "M1_3") (pintype "passive"))
      (node (ref "Y轴A498模块") (pin "4") (pinfunction "M2_4") (pintype "passive"))
    )
    (net (code "82") (name "unconnected-(MBluetooth-AIO0-Pad9)") (class "Default")
      (node (ref "MBluetooth") (pin "9") (pinfunction "AIO0_9") (pintype "passive+no_connect"))
    )
    (net (code "83") (name "unconnected-(MBluetooth-AIO1-Pad10)") (class "Default")
      (node (ref "MBluetooth") (pin "10") (pinfunction "AIO1_10") (pintype "passive+no_connect"))
    )
    (net (code "84") (name "unconnected-(MBluetooth-CLK-Pad19)") (class "Default")
      (node (ref "MBluetooth") (pin "19") (pinfunction "CLK_19") (pintype "passive+no_connect"))
    )
    (net (code "85") (name "unconnected-(MBluetooth-CSB-Pad16)") (class "Default")
      (node (ref "MBluetooth") (pin "16") (pinfunction "CSB_16") (pintype "passive+no_connect"))
    )
    (net (code "86") (name "unconnected-(MBluetooth-CTS-Pad3)") (class "Default")
      (node (ref "MBluetooth") (pin "3") (pinfunction "CTS_3") (pintype "passive+no_connect"))
    )
    (net (code "87") (name "unconnected-(MBluetooth-GND-Pad21)") (class "Default")
      (node (ref "MBluetooth") (pin "21") (pinfunction "GND_21") (pintype "passive+no_connect"))
    )
    (net (code "88") (name "unconnected-(MBluetooth-MISO-Pad18)") (class "Default")
      (node (ref "MBluetooth") (pin "18") (pinfunction "MISO_18") (pintype "passive+no_connect"))
    )
    (net (code "89") (name "unconnected-(MBluetooth-MOSI-Pad17)") (class "Default")
      (node (ref "MBluetooth") (pin "17") (pinfunction "MOSI_17") (pintype "passive+no_connect"))
    )
    (net (code "90") (name "unconnected-(MBluetooth-NC-Pad14)") (class "Default")
      (node (ref "MBluetooth") (pin "14") (pinfunction "NC_14") (pintype "passive+no_connect"))
    )
    (net (code "91") (name "unconnected-(MBluetooth-PCM_CLK-Pad5)") (class "Default")
      (node (ref "MBluetooth") (pin "5") (pinfunction "PCM_CLK_5") (pintype "passive+no_connect"))
    )
    (net (code "92") (name "unconnected-(MBluetooth-PCM_IN-Pad7)") (class "Default")
      (node (ref "MBluetooth") (pin "7") (pinfunction "PCM_IN_7") (pintype "passive+no_connect"))
    )
    (net (code "93") (name "unconnected-(MBluetooth-PCM_OUT-Pad6)") (class "Default")
      (node (ref "MBluetooth") (pin "6") (pinfunction "PCM_OUT_6") (pintype "passive+no_connect"))
    )
    (net (code "94") (name "unconnected-(MBluetooth-PCM_SYNC-Pad8)") (class "Default")
      (node (ref "MBluetooth") (pin "8") (pinfunction "PCM_SYNC_8") (pintype "passive+no_connect"))
    )
    (net (code "95") (name "unconnected-(MBluetooth-PIO0-Pad23)") (class "Default")
      (node (ref "MBluetooth") (pin "23") (pinfunction "PIO0_23") (pintype "passive+no_connect"))
    )
    (net (code "96") (name "unconnected-(MBluetooth-PIO2-Pad25)") (class "Default")
      (node (ref "MBluetooth") (pin "25") (pinfunction "PIO2_25") (pintype "passive+no_connect"))
    )
    (net (code "97") (name "unconnected-(MBluetooth-PIO4-Pad27)") (class "Default")
      (node (ref "MBluetooth") (pin "27") (pinfunction "PIO4_27") (pintype "passive+no_connect"))
    )
    (net (code "98") (name "unconnected-(MBluetooth-PIO5-Pad28)") (class "Default")
      (node (ref "MBluetooth") (pin "28") (pinfunction "PIO5_28") (pintype "passive+no_connect"))
    )
    (net (code "99") (name "unconnected-(MBluetooth-PIO6-Pad29)") (class "Default")
      (node (ref "MBluetooth") (pin "29") (pinfunction "PIO6_29") (pintype "passive+no_connect"))
    )
    (net (code "100") (name "unconnected-(MBluetooth-PIO7-Pad30)") (class "Default")
      (node (ref "MBluetooth") (pin "30") (pinfunction "PIO7_30") (pintype "passive+no_connect"))
    )
    (net (code "101") (name "unconnected-(MBluetooth-PIO8-Pad31)") (class "Default")
      (node (ref "MBluetooth") (pin "31") (pinfunction "PIO8_31") (pintype "passive+no_connect"))
    )
    (net (code "102") (name "unconnected-(MBluetooth-PIO9-Pad32)") (class "Default")
      (node (ref "MBluetooth") (pin "32") (pinfunction "PIO9_32") (pintype "passive+no_connect"))
    )
    (net (code "103") (name "unconnected-(MBluetooth-PIO10-Pad33)") (class "Default")
      (node (ref "MBluetooth") (pin "33") (pinfunction "PIO10_33") (pintype "passive+no_connect"))
    )
    (net (code "104") (name "unconnected-(MBluetooth-PIO11-Pad34)") (class "Default")
      (node (ref "MBluetooth") (pin "34") (pinfunction "PIO11_34") (pintype "passive+no_connect"))
    )
    (net (code "105") (name "unconnected-(MBluetooth-RESET-Pad11)") (class "Default")
      (node (ref "MBluetooth") (pin "11") (pinfunction "RESET_11") (pintype "passive+no_connect"))
    )
    (net (code "106") (name "unconnected-(MBluetooth-RT3-Pad4)") (class "Default")
      (node (ref "MBluetooth") (pin "4") (pinfunction "RT3_4") (pintype "passive+no_connect"))
    )
    (net (code "107") (name "unconnected-(MBluetooth-USB_D+-Pad20)") (class "Default")
      (node (ref "MBluetooth") (pin "20") (pinfunction "USB_D+_20") (pintype "passive+no_connect"))
    )
    (net (code "108") (name "unconnected-(MBluetooth-USB_D--Pad15)") (class "Default")
      (node (ref "MBluetooth") (pin "15") (pinfunction "USB_D-_15") (pintype "passive+no_connect"))
    )
    (net (code "109") (name "unconnected-(SW1-COM2-Pad5)") (class "Default")
      (node (ref "SW1") (pin "5") (pinfunction "COM2_5") (pintype "passive"))
    )
    (net (code "110") (name "unconnected-(SW1-NC1-Pad1)") (class "Default")
      (node (ref "SW1") (pin "1") (pinfunction "NC1_1") (pintype "passive"))
    )
    (net (code "111") (name "unconnected-(SW1-NC2-Pad6)") (class "Default")
      (node (ref "SW1") (pin "6") (pinfunction "NC2_6") (pintype "passive"))
    )
    (net (code "112") (name "unconnected-(SW1-NO2-Pad4)") (class "Default")
      (node (ref "SW1") (pin "4") (pinfunction "NO2_4") (pintype "passive"))
    )
    (net (code "113") (name "unconnected-(SWMode-NC1-Pad1)") (class "Default")
      (node (ref "SWMode") (pin "1") (pinfunction "NC1_1") (pintype "passive"))
    )
    (net (code "114") (name "unconnected-(SWMode-NC2-Pad6)") (class "Default")
      (node (ref "SWMode") (pin "6") (pinfunction "NC2_6") (pintype "passive"))
    )
  )
)
